# USB.net
KiCad netlist of a schematic drawn in Altium Designer
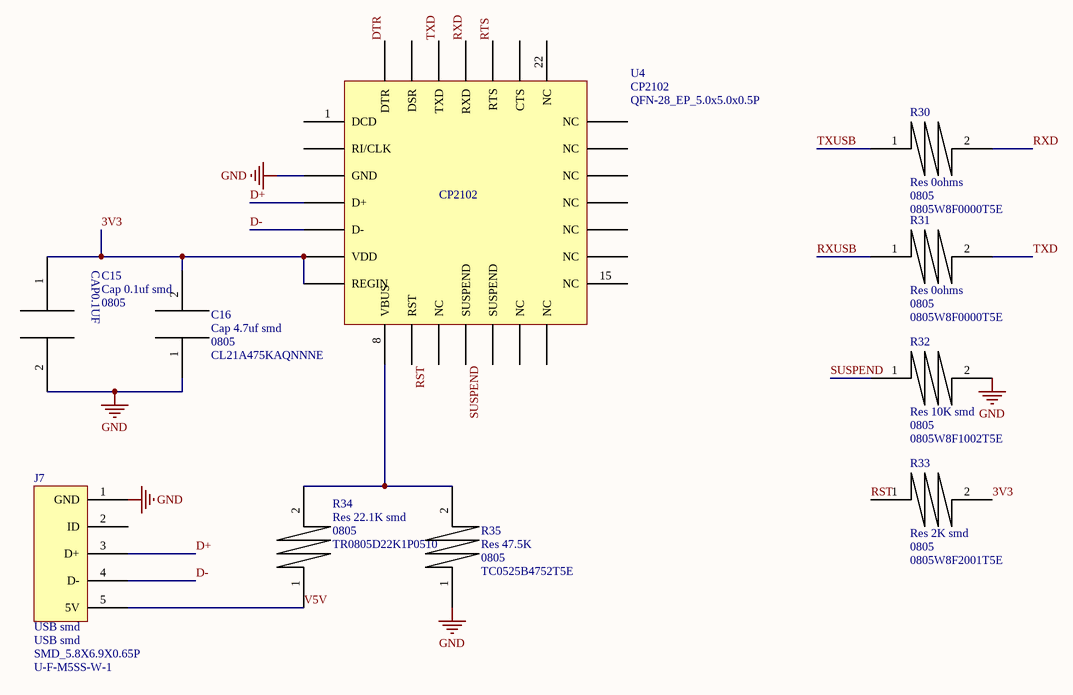
[diagram p0: USB.SchDoc]

(export (version "E")
  (design (tool "Eeschema 10.0.6"))
  (components
    (comp (ref "C15")
      (value "Cap 0.1uf smd")
      (footprint "CAP0.1UFSMD")
      (description "0.1uf")
      (fields (field (name "PACKAGE") "0805"))
      (libsource (lib "Integrated_Library") (part "Cap 0.1uf smd"))
    )
    (comp (ref "C16")
      (value "Cap 4.7uf smd")
      (footprint "CAP4.7UFSMD")
      (description "4.7uf")
      (fields (field (name "PACKAGE") "0805") (field (name "MFR.PART #") "CL21A475KAQNNNE"))
      (libsource (lib "Integrated_Library") (part "Cap 4.7uf smd"))
    )
    (comp (ref "J7")
      (value "USB smd")
      (footprint "USB smd")
      (fields (field (name "PACKAGE") "SMD_5.8X6.9X0.65P") (field (name "MFR.PART #") "U-F-M5SS-W-1"))
      (libsource (lib "Integrated_Library") (part "USB smd"))
    )
    (comp (ref "R30")
      (value "Res 0ohms")
      (footprint "RES 0 Ohms")
      (fields (field (name "PACKAGE") "0805") (field (name "MFR.PART #") "0805W8F0000T5E"))
      (libsource (lib "Integrated_Library") (part "Res 0ohms"))
    )
    (comp (ref "R31")
      (value "Res 0ohms")
      (footprint "RES 0 Ohms")
      (fields (field (name "PACKAGE") "0805") (field (name "MFR.PART #") "0805W8F0000T5E"))
      (libsource (lib "Integrated_Library") (part "Res 0ohms"))
    )
    (comp (ref "R32")
      (value "Res 10K smd")
      (footprint "RES 10K")
      (description "10K")
      (fields (field (name "PACKAGE") "0805") (field (name "MFR.PART #") "0805W8F1002T5E"))
      (libsource (lib "Integrated_Library") (part "Res 10K smd"))
    )
    (comp (ref "R33")
      (value "Res 2K smd")
      (footprint "RES 2K")
      (description "2K")
      (fields (field (name "PACKAGE") "0805") (field (name "MFR.PART #") "0805W8F2001T5E"))
      (libsource (lib "Integrated_Library") (part "Res 2K smd"))
    )
    (comp (ref "R34")
      (value "Res 22.1K smd")
      (footprint "RES 22.1K")
      (description "22.1K")
      (fields (field (name "PACKAGE") "0805") (field (name "MFR.PART #") "TR0805D22K1P0510"))
      (libsource (lib "Integrated_Library") (part "Res 22.1K smd"))
    )
    (comp (ref "R35")
      (value "Res 47.5K")
      (footprint "RES 47.5K")
      (description "47.5K")
      (fields (field (name "PACKAGE") "0805") (field (name "MFR.PART #") "TC0525B4752T5E"))
      (libsource (lib "Integrated_Library") (part "Res 47.5K"))
    )
    (comp (ref "U4")
      (value "CP2102")
      (footprint "CP2102")
      (fields (field (name "PACKAGE") "QFN-28_EP_5.0x5.0x0.5P"))
      (libsource (lib "Integrated_Library") (part "CP2102"))
    )
  )
  (nets
    (net (code "1") (name "/3V3") (class "Default")
      (node (ref "C15") (pin "1") (pinfunction "1_1") (pintype "passive"))
      (node (ref "C16") (pin "2") (pinfunction "2_2") (pintype "passive"))
      (node (ref "R33") (pin "2") (pinfunction "2_2") (pintype "passive"))
      (node (ref "U4") (pin "6") (pinfunction "VDD_6") (pintype "passive"))
      (node (ref "U4") (pin "7") (pinfunction "REGIN_7") (pintype "passive"))
    )
    (net (code "2") (name "/D+") (class "Default")
      (node (ref "J7") (pin "3") (pinfunction "D+_3") (pintype "passive"))
      (node (ref "U4") (pin "4") (pinfunction "D+_4") (pintype "passive"))
    )
    (net (code "3") (name "/D-") (class "Default")
      (node (ref "J7") (pin "4") (pinfunction "D-_4") (pintype "passive"))
      (node (ref "U4") (pin "5") (pinfunction "D-_5") (pintype "passive"))
    )
    (net (code "4") (name "/DTR") (class "Default")
      (node (ref "U4") (pin "28") (pinfunction "DTR_28") (pintype "passive"))
    )
    (net (code "5") (name "/RST") (class "Default")
      (node (ref "R33") (pin "1") (pinfunction "1_1") (pintype "passive"))
      (node (ref "U4") (pin "9") (pinfunction "RST_9") (pintype "passive"))
    )
    (net (code "6") (name "/RTS") (class "Default")
      (node (ref "U4") (pin "24") (pinfunction "RTS_24") (pintype "passive"))
    )
    (net (code "7") (name "/RXD") (class "Default")
      (node (ref "R30") (pin "2") (pinfunction "2_2") (pintype "passive"))
      (node (ref "U4") (pin "25") (pinfunction "RXD_25") (pintype "passive"))
    )
    (net (code "8") (name "/RXUSB") (class "Default")
      (node (ref "R31") (pin "1") (pinfunction "1_1") (pintype "passive"))
    )
    (net (code "9") (name "/SUSPEND") (class "Default")
      (node (ref "R32") (pin "1") (pinfunction "1_1") (pintype "passive"))
      (node (ref "U4") (pin "11") (pinfunction "SUSPEND_11") (pintype "passive"))
    )
    (net (code "10") (name "/TXD") (class "Default")
      (node (ref "R31") (pin "2") (pinfunction "2_2") (pintype "passive"))
      (node (ref "U4") (pin "26") (pinfunction "TXD_26") (pintype "passive"))
    )
    (net (code "11") (name "/TXUSB") (class "Default")
      (node (ref "R30") (pin "1") (pinfunction "1_1") (pintype "passive"))
    )
    (net (code "12") (name "/V5V") (class "Default")
      (node (ref "J7") (pin "5") (pinfunction "5V_5") (pintype "passive"))
      (node (ref "R34") (pin "1") (pinfunction "1_1") (pintype "passive"))
    )
    (net (code "13") (name "GND") (class "Default")
      (node (ref "C15") (pin "2") (pinfunction "2_2") (pintype "passive"))
      (node (ref "C16") (pin "1") (pinfunction "1_1") (pintype "passive"))
      (node (ref "J7") (pin "1") (pinfunction "GND_1") (pintype "passive"))
      (node (ref "R32") (pin "2") (pinfunction "2_2") (pintype "passive"))
      (node (ref "R35") (pin "1") (pinfunction "1_1") (pintype "passive"))
      (node (ref "U4") (pin "3") (pinfunction "GND_3") (pintype "passive"))
    )
    (net (code "14") (name "Net-(U4-VBUS)") (class "Default")
      (node (ref "R34") (pin "2") (pinfunction "2_2") (pintype "passive"))
      (node (ref "R35") (pin "2") (pinfunction "2_2") (pintype "passive"))
      (node (ref "U4") (pin "8") (pinfunction "VBUS_8") (pintype "passive"))
    )
    (net (code "15") (name "unconnected-(J7-ID-Pad2)") (class "Default")
      (node (ref "J7") (pin "2") (pinfunction "ID_2") (pintype "passive"))
    )
    (net (code "16") (name "unconnected-(U4-CTS-Pad23)") (class "Default")
      (node (ref "U4") (pin "23") (pinfunction "CTS_23") (pintype "passive"))
    )
    (net (code "17") (name "unconnected-(U4-DCD-Pad1)") (class "Default")
      (node (ref "U4") (pin "1") (pinfunction "DCD_1") (pintype "passive"))
    )
    (net (code "18") (name "unconnected-(U4-DSR-Pad27)") (class "Default")
      (node (ref "U4") (pin "27") (pinfunction "DSR_27") (pintype "passive"))
    )
    (net (code "19") (name "unconnected-(U4-NC-Pad10)") (class "Default")
      (node (ref "U4") (pin "10") (pinfunction "NC_10") (pintype "passive"))
    )
    (net (code "20") (name "unconnected-(U4-NC-Pad13)") (class "Default")
      (node (ref "U4") (pin "13") (pinfunction "NC_13") (pintype "passive"))
    )
    (net (code "21") (name "unconnected-(U4-NC-Pad14)") (class "Default")
      (node (ref "U4") (pin "14") (pinfunction "NC_14") (pintype "passive"))
    )
    (net (code "22") (name "unconnected-(U4-NC-Pad15)") (class "Default")
      (node (ref "U4") (pin "15") (pinfunction "NC_15") (pintype "passive"))
    )
    (net (code "23") (name "unconnected-(U4-NC-Pad16)") (class "Default")
      (node (ref "U4") (pin "16") (pinfunction "NC_16") (pintype "passive"))
    )
    (net (code "24") (name "unconnected-(U4-NC-Pad17)") (class "Default")
      (node (ref "U4") (pin "17") (pinfunction "NC_17") (pintype "passive"))
    )
    (net (code "25") (name "unconnected-(U4-NC-Pad18)") (class "Default")
      (node (ref "U4") (pin "18") (pinfunction "NC_18") (pintype "passive"))
    )
    (net (code "26") (name "unconnected-(U4-NC-Pad19)") (class "Default")
      (node (ref "U4") (pin "19") (pinfunction "NC_19") (pintype "passive"))
    )
    (net (code "27") (name "unconnected-(U4-NC-Pad20)") (class "Default")
      (node (ref "U4") (pin "20") (pinfunction "NC_20") (pintype "passive"))
    )
    (net (code "28") (name "unconnected-(U4-NC-Pad21)") (class "Default")
      (node (ref "U4") (pin "21") (pinfunction "NC_21") (pintype "passive"))
    )
    (net (code "29") (name "unconnected-(U4-NC-Pad22)") (class "Default")
      (node (ref "U4") (pin "22") (pinfunction "NC_22") (pintype "passive"))
    )
    (net (code "30") (name "unconnected-(U4-RI{slash}CLK-Pad2)") (class "Default")
      (node (ref "U4") (pin "2") (pinfunction "RI/CLK_2") (pintype "passive"))
    )
    (net (code "31") (name "unconnected-(U4-SUSPEND-Pad12)") (class "Default")
      (node (ref "U4") (pin "12") (pinfunction "SUSPEND_12") (pintype "passive"))
    )
  )
)
